# display_driver.net
KiCad netlist of a schematic drawn in EAGLE
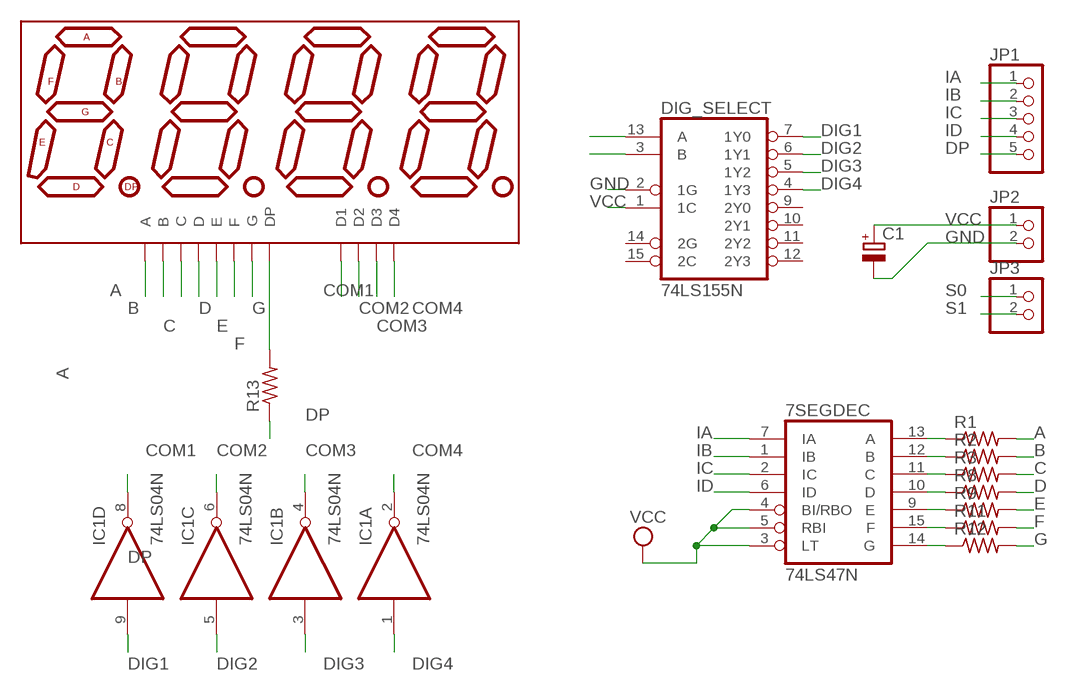
[diagram p0: schematic, sheet 1]

(export (version "E")
  (design (tool "Eeschema 10.0.6"))
  (components
    (comp (ref "7SEGDEC")
      (value "74LS47N")
      (footprint "eagle-import:DIL16")
      (libsource (lib "eagle-import") (part "7447NLS"))
    )
    (comp (ref "C1")
      (value "CPOL-EUE2-5")
      (footprint "eagle-import:E2-5")
      (libsource (lib "eagle-import") (part "CPOL-EUE2-5"))
    )
    (comp (ref "DIG_SELECT")
      (value "74LS155N")
      (footprint "eagle-import:DIL16")
      (libsource (lib "eagle-import") (part "74155NLS"))
    )
    (comp (ref "DISP1")
      (value "7-SEGMENT-4DIGIT-COUNTERCL5642BH-33")
      (footprint "eagle-import:4DIG_CA")
      (libsource (lib "eagle-import") (part "7-SEGMENT-4DIGIT-COUNTERCL5642BH-33"))
    )
    (comp (ref "IC1")
      (value "74LS04N")
      (footprint "eagle-import:DIL14")
      (libsource (lib "eagle-import") (part "7404NLS"))
    )
    (comp (ref "JP1")
      (value "PINHD-1X5")
      (footprint "eagle-import:1X05")
      (libsource (lib "eagle-import") (part "PINHD-1X5"))
    )
    (comp (ref "JP2")
      (value "PINHD-1X2")
      (footprint "eagle-import:1X02")
      (libsource (lib "eagle-import") (part "PINHD-1X2"))
    )
    (comp (ref "JP3")
      (value "PINHD-1X2")
      (footprint "eagle-import:1X02")
      (libsource (lib "eagle-import") (part "PINHD-1X2"))
    )
    (comp (ref "R1")
      (value "R-US_0204/7")
      (footprint "eagle-import:0204_7")
      (libsource (lib "eagle-import") (part "R-US_0204/7"))
    )
    (comp (ref "R2")
      (value "R-US_0204/7")
      (footprint "eagle-import:0204_7")
      (libsource (lib "eagle-import") (part "R-US_0204/7"))
    )
    (comp (ref "R3")
      (value "R-US_0204/7")
      (footprint "eagle-import:0204_7")
      (libsource (lib "eagle-import") (part "R-US_0204/7"))
    )
    (comp (ref "R8")
      (value "R-US_0204/7")
      (footprint "eagle-import:0204_7")
      (libsource (lib "eagle-import") (part "R-US_0204/7"))
    )
    (comp (ref "R9")
      (value "R-US_0204/7")
      (footprint "eagle-import:0204_7")
      (libsource (lib "eagle-import") (part "R-US_0204/7"))
    )
    (comp (ref "R11")
      (value "R-US_0204/7")
      (footprint "eagle-import:0204_7")
      (libsource (lib "eagle-import") (part "R-US_0204/7"))
    )
    (comp (ref "R12")
      (value "R-US_0204/7")
      (footprint "eagle-import:0204_7")
      (libsource (lib "eagle-import") (part "R-US_0204/7"))
    )
    (comp (ref "R13")
      (value "R-US_0204/7")
      (footprint "eagle-import:0204_7")
      (libsource (lib "eagle-import") (part "R-US_0204/7"))
    )
  )
  (nets
    (net (code "1") (name "/A") (class "Default")
      (node (ref "DISP1") (pin "A") (pinfunction "A_A") (pintype "bidirectional"))
      (node (ref "R1") (pin "2") (pinfunction "2_2") (pintype "passive"))
    )
    (net (code "2") (name "/B") (class "Default")
      (node (ref "DISP1") (pin "B") (pinfunction "B_B") (pintype "bidirectional"))
      (node (ref "R2") (pin "2") (pinfunction "2_2") (pintype "passive"))
    )
    (net (code "3") (name "/C") (class "Default")
      (node (ref "DISP1") (pin "C") (pinfunction "C_C") (pintype "bidirectional"))
      (node (ref "R3") (pin "2") (pinfunction "2_2") (pintype "passive"))
    )
    (net (code "4") (name "/COM1") (class "Default")
      (node (ref "DISP1") (pin "COM1") (pinfunction "D1_COM1") (pintype "bidirectional"))
      (node (ref "IC1") (pin "8") (pinfunction "O_8") (pintype "output"))
    )
    (net (code "5") (name "/COM2") (class "Default")
      (node (ref "DISP1") (pin "COM2") (pinfunction "D2_COM2") (pintype "bidirectional"))
      (node (ref "IC1") (pin "6") (pinfunction "O_6") (pintype "output"))
    )
    (net (code "6") (name "/COM3") (class "Default")
      (node (ref "DISP1") (pin "COM3") (pinfunction "D3_COM3") (pintype "bidirectional"))
      (node (ref "IC1") (pin "4") (pinfunction "O_4") (pintype "output"))
    )
    (net (code "7") (name "/COM4") (class "Default")
      (node (ref "DISP1") (pin "COM4") (pinfunction "D4_COM4") (pintype "bidirectional"))
      (node (ref "IC1") (pin "2") (pinfunction "O_2") (pintype "output"))
    )
    (net (code "8") (name "/D") (class "Default")
      (node (ref "DISP1") (pin "D") (pinfunction "D_D") (pintype "bidirectional"))
      (node (ref "R8") (pin "2") (pinfunction "2_2") (pintype "passive"))
    )
    (net (code "9") (name "/DIG1") (class "Default")
      (node (ref "DIG_SELECT") (pin "7") (pinfunction "1Y0_7") (pintype "output"))
      (node (ref "IC1") (pin "9") (pinfunction "I_9") (pintype "input"))
    )
    (net (code "10") (name "/DIG2") (class "Default")
      (node (ref "DIG_SELECT") (pin "6") (pinfunction "1Y1_6") (pintype "output"))
      (node (ref "IC1") (pin "5") (pinfunction "I_5") (pintype "input"))
    )
    (net (code "11") (name "/DIG3") (class "Default")
      (node (ref "DIG_SELECT") (pin "5") (pinfunction "1Y2_5") (pintype "output"))
      (node (ref "IC1") (pin "3") (pinfunction "I_3") (pintype "input"))
    )
    (net (code "12") (name "/DIG4") (class "Default")
      (node (ref "DIG_SELECT") (pin "4") (pinfunction "1Y3_4") (pintype "output"))
      (node (ref "IC1") (pin "1") (pinfunction "I_1") (pintype "input"))
    )
    (net (code "13") (name "/DP") (class "Default")
      (node (ref "JP1") (pin "5") (pinfunction "5_5") (pintype "passive"))
      (node (ref "R13") (pin "1") (pinfunction "1_1") (pintype "passive"))
    )
    (net (code "14") (name "/E") (class "Default")
      (node (ref "DISP1") (pin "E") (pinfunction "E_E") (pintype "bidirectional"))
      (node (ref "R9") (pin "2") (pinfunction "2_2") (pintype "passive"))
    )
    (net (code "15") (name "/F") (class "Default")
      (node (ref "DISP1") (pin "F") (pinfunction "F_F") (pintype "bidirectional"))
      (node (ref "R11") (pin "2") (pinfunction "2_2") (pintype "passive"))
    )
    (net (code "16") (name "/G") (class "Default")
      (node (ref "DISP1") (pin "G") (pinfunction "G_G") (pintype "bidirectional"))
      (node (ref "R12") (pin "2") (pinfunction "2_2") (pintype "passive"))
    )
    (net (code "17") (name "/GND") (class "Default")
      (node (ref "C1") (pin "-") (pinfunction "-_-") (pintype "passive"))
      (node (ref "DIG_SELECT") (pin "2") (pinfunction "1G_2") (pintype "input"))
      (node (ref "JP2") (pin "2") (pinfunction "2_2") (pintype "passive"))
    )
    (net (code "18") (name "/IA") (class "Default")
      (node (ref "7SEGDEC") (pin "7") (pinfunction "IA_7") (pintype "input"))
      (node (ref "JP1") (pin "1") (pinfunction "1_1") (pintype "passive"))
    )
    (net (code "19") (name "/IB") (class "Default")
      (node (ref "7SEGDEC") (pin "1") (pinfunction "IB_1") (pintype "input"))
      (node (ref "JP1") (pin "2") (pinfunction "2_2") (pintype "passive"))
    )
    (net (code "20") (name "/IC") (class "Default")
      (node (ref "7SEGDEC") (pin "2") (pinfunction "IC_2") (pintype "input"))
      (node (ref "JP1") (pin "3") (pinfunction "3_3") (pintype "passive"))
    )
    (net (code "21") (name "/ID") (class "Default")
      (node (ref "7SEGDEC") (pin "6") (pinfunction "ID_6") (pintype "input"))
      (node (ref "JP1") (pin "4") (pinfunction "4_4") (pintype "passive"))
    )
    (net (code "22") (name "/S0") (class "Default")
      (node (ref "DIG_SELECT") (pin "13") (pinfunction "A_13") (pintype "input"))
      (node (ref "JP3") (pin "1") (pinfunction "1_1") (pintype "passive"))
    )
    (net (code "23") (name "/S1") (class "Default")
      (node (ref "DIG_SELECT") (pin "3") (pinfunction "B_3") (pintype "input"))
      (node (ref "JP3") (pin "2") (pinfunction "2_2") (pintype "passive"))
    )
    (net (code "24") (name "Net-(7SEGDECA-A)") (class "Default")
      (node (ref "7SEGDEC") (pin "13") (pinfunction "A_13") (pintype "output"))
      (node (ref "R1") (pin "1") (pinfunction "1_1") (pintype "passive"))
    )
    (net (code "25") (name "Net-(7SEGDECA-B)") (class "Default")
      (node (ref "7SEGDEC") (pin "12") (pinfunction "B_12") (pintype "output"))
      (node (ref "R2") (pin "1") (pinfunction "1_1") (pintype "passive"))
    )
    (net (code "26") (name "Net-(7SEGDECA-C)") (class "Default")
      (node (ref "7SEGDEC") (pin "11") (pinfunction "C_11") (pintype "output"))
      (node (ref "R3") (pin "1") (pinfunction "1_1") (pintype "passive"))
    )
    (net (code "27") (name "Net-(7SEGDECA-D)") (class "Default")
      (node (ref "7SEGDEC") (pin "10") (pinfunction "D_10") (pintype "output"))
      (node (ref "R8") (pin "1") (pinfunction "1_1") (pintype "passive"))
    )
    (net (code "28") (name "Net-(7SEGDECA-E)") (class "Default")
      (node (ref "7SEGDEC") (pin "9") (pinfunction "E_9") (pintype "output"))
      (node (ref "R9") (pin "1") (pinfunction "1_1") (pintype "passive"))
    )
    (net (code "29") (name "Net-(7SEGDECA-F)") (class "Default")
      (node (ref "7SEGDEC") (pin "15") (pinfunction "F_15") (pintype "output"))
      (node (ref "R11") (pin "1") (pinfunction "1_1") (pintype "passive"))
    )
    (net (code "30") (name "Net-(7SEGDECA-G)") (class "Default")
      (node (ref "7SEGDEC") (pin "14") (pinfunction "G_14") (pintype "output"))
      (node (ref "R12") (pin "1") (pinfunction "1_1") (pintype "passive"))
    )
    (net (code "31") (name "Net-(DISP1-PadDP)") (class "Default")
      (node (ref "DISP1") (pin "DP") (pinfunction "DP_DP") (pintype "bidirectional"))
      (node (ref "R13") (pin "2") (pinfunction "2_2") (pintype "passive"))
    )
    (net (code "32") (name "VCC") (class "Default")
      (node (ref "7SEGDEC") (pin "3") (pinfunction "LT_3") (pintype "input"))
      (node (ref "7SEGDEC") (pin "4") (pinfunction "BI/RBO_4") (pintype "input"))
      (node (ref "7SEGDEC") (pin "5") (pinfunction "RBI_5") (pintype "input"))
      (node (ref "C1") (pin "+") (pinfunction "+_+") (pintype "passive"))
      (node (ref "DIG_SELECT") (pin "1") (pinfunction "1C_1") (pintype "input"))
      (node (ref "JP2") (pin "1") (pinfunction "1_1") (pintype "passive"))
    )
    (net (code "33") (name "unconnected-(DIG_SELECTA-2C-Pad15)") (class "Default")
      (node (ref "DIG_SELECT") (pin "15") (pinfunction "2C_15") (pintype "input"))
    )
    (net (code "34") (name "unconnected-(DIG_SELECTA-2G-Pad14)") (class "Default")
      (node (ref "DIG_SELECT") (pin "14") (pinfunction "2G_14") (pintype "input"))
    )
    (net (code "35") (name "unconnected-(DIG_SELECTA-2Y0-Pad9)") (class "Default")
      (node (ref "DIG_SELECT") (pin "9") (pinfunction "2Y0_9") (pintype "output"))
    )
    (net (code "36") (name "unconnected-(DIG_SELECTA-2Y1-Pad10)") (class "Default")
      (node (ref "DIG_SELECT") (pin "10") (pinfunction "2Y1_10") (pintype "output"))
    )
    (net (code "37") (name "unconnected-(DIG_SELECTA-2Y2-Pad11)") (class "Default")
      (node (ref "DIG_SELECT") (pin "11") (pinfunction "2Y2_11") (pintype "output"))
    )
    (net (code "38") (name "unconnected-(DIG_SELECTA-2Y3-Pad12)") (class "Default")
      (node (ref "DIG_SELECT") (pin "12") (pinfunction "2Y3_12") (pintype "output"))
    )
  )
)
